# Facef.net
KiCad netlist of a schematic drawn in EAGLE
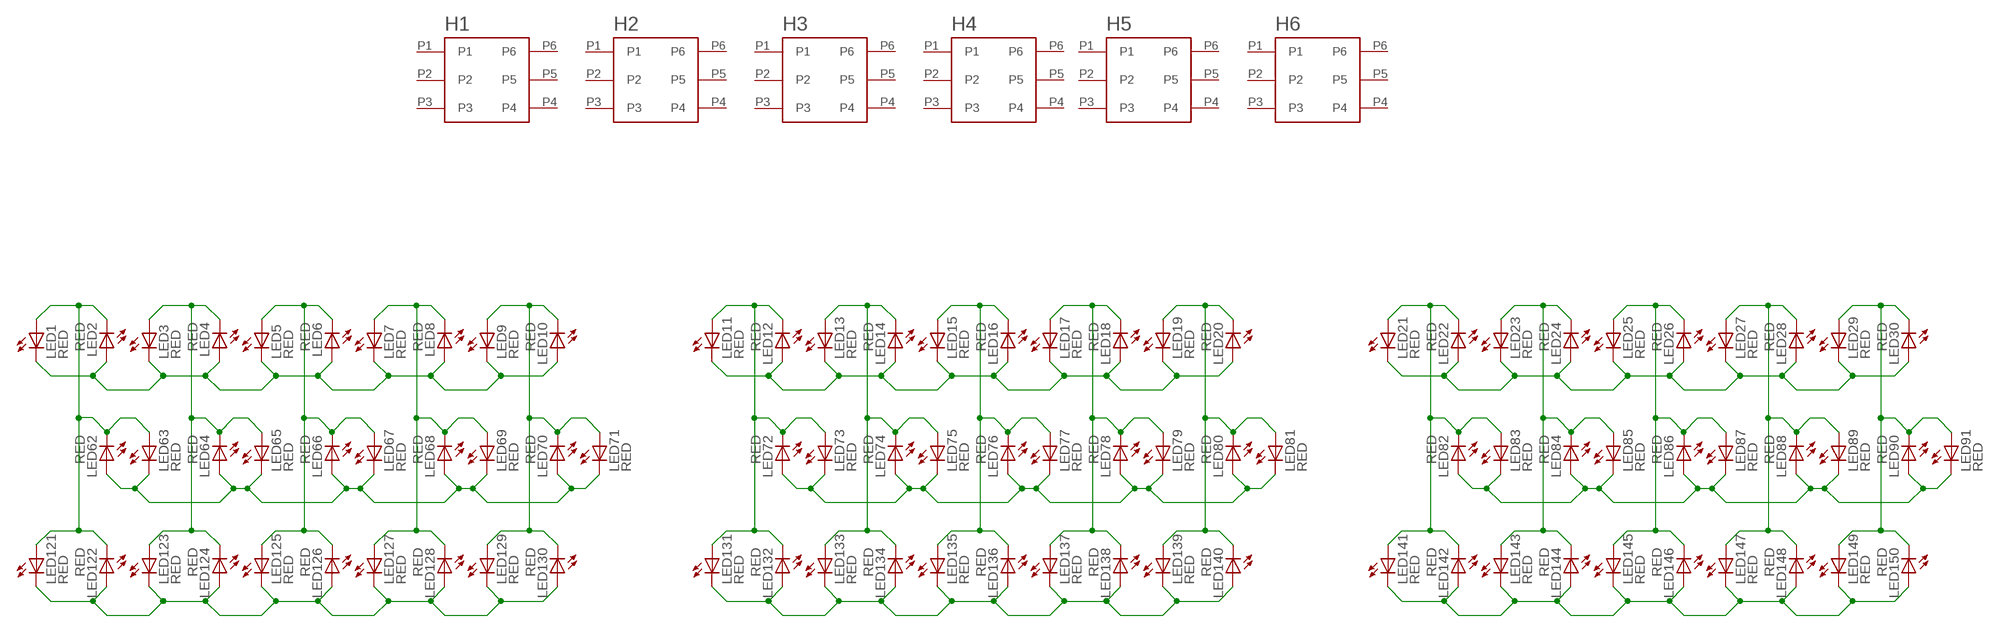
[diagram p0: schematic, sheet 1, part 1 of 2]
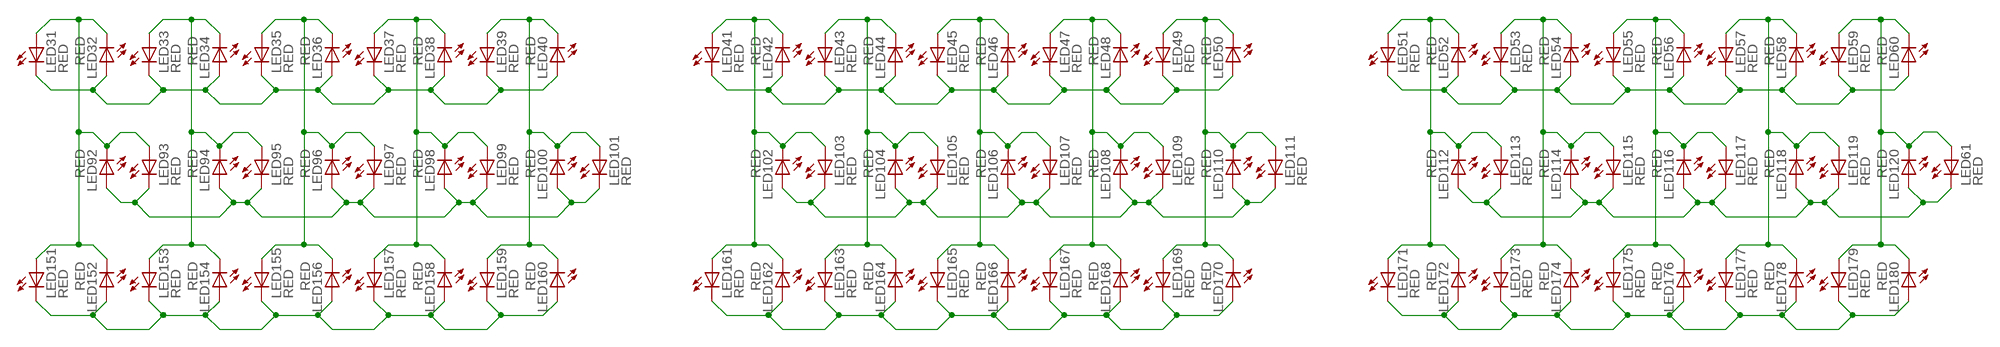
[diagram p1: schematic, sheet 1, part 2 of 2]

(export (version "E")
  (design (tool "Eeschema 10.0.6"))
  (components
    (comp (ref "H1")
      (value "2X3")
      (footprint "eagle-import:3X2_1MM_SMD")
      (libsource (lib "eagle-import") (part "2X3"))
    )
    (comp (ref "H2")
      (value "2X3")
      (footprint "eagle-import:3X2_1MM_SMD")
      (libsource (lib "eagle-import") (part "2X3"))
    )
    (comp (ref "H3")
      (value "2X3")
      (footprint "eagle-import:3X2_1MM_SMD")
      (libsource (lib "eagle-import") (part "2X3"))
    )
    (comp (ref "H4")
      (value "2X3")
      (footprint "eagle-import:3X2_1MM_SMD")
      (libsource (lib "eagle-import") (part "2X3"))
    )
    (comp (ref "H5")
      (value "2X3")
      (footprint "eagle-import:3X2_1MM_SMD")
      (libsource (lib "eagle-import") (part "2X3"))
    )
    (comp (ref "H6")
      (value "2X3")
      (footprint "eagle-import:3X2_1MM_SMD")
      (libsource (lib "eagle-import") (part "2X3"))
    )
    (comp (ref "LED1")
      (value "RED")
      (footprint "eagle-import:LED-0603")
      (libsource (lib "eagle-import") (part "LED0603"))
    )
    (comp (ref "LED2")
      (value "RED")
      (footprint "eagle-import:LED-0603")
      (libsource (lib "eagle-import") (part "LED0603"))
    )
    (comp (ref "LED3")
      (value "RED")
      (footprint "eagle-import:LED-0603")
      (libsource (lib "eagle-import") (part "LED0603"))
    )
    (comp (ref "LED4")
      (value "RED")
      (footprint "eagle-import:LED-0603")
      (libsource (lib "eagle-import") (part "LED0603"))
    )
    (comp (ref "LED5")
      (value "RED")
      (footprint "eagle-import:LED-0603")
      (libsource (lib "eagle-import") (part "LED0603"))
    )
    (comp (ref "LED6")
      (value "RED")
      (footprint "eagle-import:LED-0603")
      (libsource (lib "eagle-import") (part "LED0603"))
    )
    (comp (ref "LED7")
      (value "RED")
      (footprint "eagle-import:LED-0603")
      (libsource (lib "eagle-import") (part "LED0603"))
    )
    (comp (ref "LED8")
      (value "RED")
      (footprint "eagle-import:LED-0603")
      (libsource (lib "eagle-import") (part "LED0603"))
    )
    (comp (ref "LED9")
      (value "RED")
      (footprint "eagle-import:LED-0603")
      (libsource (lib "eagle-import") (part "LED0603"))
    )
    (comp (ref "LED10")
      (value "RED")
      (footprint "eagle-import:LED-0603")
      (libsource (lib "eagle-import") (part "LED0603"))
    )
    (comp (ref "LED11")
      (value "RED")
      (footprint "eagle-import:LED-0603")
      (libsource (lib "eagle-import") (part "LED0603"))
    )
    (comp (ref "LED12")
      (value "RED")
      (footprint "eagle-import:LED-0603")
      (libsource (lib "eagle-import") (part "LED0603"))
    )
    (comp (ref "LED13")
      (value "RED")
      (footprint "eagle-import:LED-0603")
      (libsource (lib "eagle-import") (part "LED0603"))
    )
    (comp (ref "LED14")
      (value "RED")
      (footprint "eagle-import:LED-0603")
      (libsource (lib "eagle-import") (part "LED0603"))
    )
    (comp (ref "LED15")
      (value "RED")
      (footprint "eagle-import:LED-0603")
      (libsource (lib "eagle-import") (part "LED0603"))
    )
    (comp (ref "LED16")
      (value "RED")
      (footprint "eagle-import:LED-0603")
      (libsource (lib "eagle-import") (part "LED0603"))
    )
    (comp (ref "LED17")
      (value "RED")
      (footprint "eagle-import:LED-0603")
      (libsource (lib "eagle-import") (part "LED0603"))
    )
    (comp (ref "LED18")
      (value "RED")
      (footprint "eagle-import:LED-0603")
      (libsource (lib "eagle-import") (part "LED0603"))
    )
    (comp (ref "LED19")
      (value "RED")
      (footprint "eagle-import:LED-0603")
      (libsource (lib "eagle-import") (part "LED0603"))
    )
    (comp (ref "LED20")
      (value "RED")
      (footprint "eagle-import:LED-0603")
      (libsource (lib "eagle-import") (part "LED0603"))
    )
    (comp (ref "LED21")
      (value "RED")
      (footprint "eagle-import:LED-0603")
      (libsource (lib "eagle-import") (part "LED0603"))
    )
    (comp (ref "LED22")
      (value "RED")
      (footprint "eagle-import:LED-0603")
      (libsource (lib "eagle-import") (part "LED0603"))
    )
    (comp (ref "LED23")
      (value "RED")
      (footprint "eagle-import:LED-0603")
      (libsource (lib "eagle-import") (part "LED0603"))
    )
    (comp (ref "LED24")
      (value "RED")
      (footprint "eagle-import:LED-0603")
      (libsource (lib "eagle-import") (part "LED0603"))
    )
    (comp (ref "LED25")
      (value "RED")
      (footprint "eagle-import:LED-0603")
      (libsource (lib "eagle-import") (part "LED0603"))
    )
    (comp (ref "LED26")
      (value "RED")
      (footprint "eagle-import:LED-0603")
      (libsource (lib "eagle-import") (part "LED0603"))
    )
    (comp (ref "LED27")
      (value "RED")
      (footprint "eagle-import:LED-0603")
      (libsource (lib "eagle-import") (part "LED0603"))
    )
    (comp (ref "LED28")
      (value "RED")
      (footprint "eagle-import:LED-0603")
      (libsource (lib "eagle-import") (part "LED0603"))
    )
    (comp (ref "LED29")
      (value "RED")
      (footprint "eagle-import:LED-0603")
      (libsource (lib "eagle-import") (part "LED0603"))
    )
    (comp (ref "LED30")
      (value "RED")
      (footprint "eagle-import:LED-0603")
      (libsource (lib "eagle-import") (part "LED0603"))
    )
    (comp (ref "LED31")
      (value "RED")
      (footprint "eagle-import:LED-0603")
      (libsource (lib "eagle-import") (part "LED0603"))
    )
    (comp (ref "LED32")
      (value "RED")
      (footprint "eagle-import:LED-0603")
      (libsource (lib "eagle-import") (part "LED0603"))
    )
    (comp (ref "LED33")
      (value "RED")
      (footprint "eagle-import:LED-0603")
      (libsource (lib "eagle-import") (part "LED0603"))
    )
    (comp (ref "LED34")
      (value "RED")
      (footprint "eagle-import:LED-0603")
      (libsource (lib "eagle-import") (part "LED0603"))
    )
    (comp (ref "LED35")
      (value "RED")
      (footprint "eagle-import:LED-0603")
      (libsource (lib "eagle-import") (part "LED0603"))
    )
    (comp (ref "LED36")
      (value "RED")
      (footprint "eagle-import:LED-0603")
      (libsource (lib "eagle-import") (part "LED0603"))
    )
    (comp (ref "LED37")
      (value "RED")
      (footprint "eagle-import:LED-0603")
      (libsource (lib "eagle-import") (part "LED0603"))
    )
    (comp (ref "LED38")
      (value "RED")
      (footprint "eagle-import:LED-0603")
      (libsource (lib "eagle-import") (part "LED0603"))
    )
    (comp (ref "LED39")
      (value "RED")
      (footprint "eagle-import:LED-0603")
      (libsource (lib "eagle-import") (part "LED0603"))
    )
    (comp (ref "LED40")
      (value "RED")
      (footprint "eagle-import:LED-0603")
      (libsource (lib "eagle-import") (part "LED0603"))
    )
    (comp (ref "LED41")
      (value "RED")
      (footprint "eagle-import:LED-0603")
      (libsource (lib "eagle-import") (part "LED0603"))
    )
    (comp (ref "LED42")
      (value "RED")
      (footprint "eagle-import:LED-0603")
      (libsource (lib "eagle-import") (part "LED0603"))
    )
    (comp (ref "LED43")
      (value "RED")
      (footprint "eagle-import:LED-0603")
      (libsource (lib "eagle-import") (part "LED0603"))
    )
    (comp (ref "LED44")
      (value "RED")
      (footprint "eagle-import:LED-0603")
      (libsource (lib "eagle-import") (part "LED0603"))
    )
    (comp (ref "LED45")
      (value "RED")
      (footprint "eagle-import:LED-0603")
      (libsource (lib "eagle-import") (part "LED0603"))
    )
    (comp (ref "LED46")
      (value "RED")
      (footprint "eagle-import:LED-0603")
      (libsource (lib "eagle-import") (part "LED0603"))
    )
    (comp (ref "LED47")
      (value "RED")
      (footprint "eagle-import:LED-0603")
      (libsource (lib "eagle-import") (part "LED0603"))
    )
    (comp (ref "LED48")
      (value "RED")
      (footprint "eagle-import:LED-0603")
      (libsource (lib "eagle-import") (part "LED0603"))
    )
    (comp (ref "LED49")
      (value "RED")
      (footprint "eagle-import:LED-0603")
      (libsource (lib "eagle-import") (part "LED0603"))
    )
    (comp (ref "LED50")
      (value "RED")
      (footprint "eagle-import:LED-0603")
      (libsource (lib "eagle-import") (part "LED0603"))
    )
    (comp (ref "LED51")
      (value "RED")
      (footprint "eagle-import:LED-0603")
      (libsource (lib "eagle-import") (part "LED0603"))
    )
    (comp (ref "LED52")
      (value "RED")
      (footprint "eagle-import:LED-0603")
      (libsource (lib "eagle-import") (part "LED0603"))
    )
    (comp (ref "LED53")
      (value "RED")
      (footprint "eagle-import:LED-0603")
      (libsource (lib "eagle-import") (part "LED0603"))
    )
    (comp (ref "LED54")
      (value "RED")
      (footprint "eagle-import:LED-0603")
      (libsource (lib "eagle-import") (part "LED0603"))
    )
    (comp (ref "LED55")
      (value "RED")
      (footprint "eagle-import:LED-0603")
      (libsource (lib "eagle-import") (part "LED0603"))
    )
    (comp (ref "LED56")
      (value "RED")
      (footprint "eagle-import:LED-0603")
      (libsource (lib "eagle-import") (part "LED0603"))
    )
    (comp (ref "LED57")
      (value "RED")
      (footprint "eagle-import:LED-0603")
      (libsource (lib "eagle-import") (part "LED0603"))
    )
    (comp (ref "LED58")
      (value "RED")
      (footprint "eagle-import:LED-0603")
      (libsource (lib "eagle-import") (part "LED0603"))
    )
    (comp (ref "LED59")
      (value "RED")
      (footprint "eagle-import:LED-0603")
      (libsource (lib "eagle-import") (part "LED0603"))
    )
    (comp (ref "LED60")
      (value "RED")
      (footprint "eagle-import:LED-0603")
      (libsource (lib "eagle-import") (part "LED0603"))
    )
    (comp (ref "LED61")
      (value "RED")
      (footprint "eagle-import:LED-0603")
      (libsource (lib "eagle-import") (part "LED0603"))
    )
    (comp (ref "LED62")
      (value "RED")
      (footprint "eagle-import:LED-0603")
      (libsource (lib "eagle-import") (part "LED0603"))
    )
    (comp (ref "LED63")
      (value "RED")
      (footprint "eagle-import:LED-0603")
      (libsource (lib "eagle-import") (part "LED0603"))
    )
    (comp (ref "LED64")
      (value "RED")
      (footprint "eagle-import:LED-0603")
      (libsource (lib "eagle-import") (part "LED0603"))
    )
    (comp (ref "LED65")
      (value "RED")
      (footprint "eagle-import:LED-0603")
      (libsource (lib "eagle-import") (part "LED0603"))
    )
    (comp (ref "LED66")
      (value "RED")
      (footprint "eagle-import:LED-0603")
      (libsource (lib "eagle-import") (part "LED0603"))
    )
    (comp (ref "LED67")
      (value "RED")
      (footprint "eagle-import:LED-0603")
      (libsource (lib "eagle-import") (part "LED0603"))
    )
    (comp (ref "LED68")
      (value "RED")
      (footprint "eagle-import:LED-0603")
      (libsource (lib "eagle-import") (part "LED0603"))
    )
    (comp (ref "LED69")
      (value "RED")
      (footprint "eagle-import:LED-0603")
      (libsource (lib "eagle-import") (part "LED0603"))
    )
    (comp (ref "LED70")
      (value "RED")
      (footprint "eagle-import:LED-0603")
      (libsource (lib "eagle-import") (part "LED0603"))
    )
    (comp (ref "LED71")
      (value "RED")
      (footprint "eagle-import:LED-0603")
      (libsource (lib "eagle-import") (part "LED0603"))
    )
    (comp (ref "LED72")
      (value "RED")
      (footprint "eagle-import:LED-0603")
      (libsource (lib "eagle-import") (part "LED0603"))
    )
    (comp (ref "LED73")
      (value "RED")
      (footprint "eagle-import:LED-0603")
      (libsource (lib "eagle-import") (part "LED0603"))
    )
    (comp (ref "LED74")
      (value "RED")
      (footprint "eagle-import:LED-0603")
      (libsource (lib "eagle-import") (part "LED0603"))
    )
    (comp (ref "LED75")
      (value "RED")
      (footprint "eagle-import:LED-0603")
      (libsource (lib "eagle-import") (part "LED0603"))
    )
    (comp (ref "LED76")
      (value "RED")
      (footprint "eagle-import:LED-0603")
      (libsource (lib "eagle-import") (part "LED0603"))
    )
    (comp (ref "LED77")
      (value "RED")
      (footprint "eagle-import:LED-0603")
      (libsource (lib "eagle-import") (part "LED0603"))
    )
    (comp (ref "LED78")
      (value "RED")
      (footprint "eagle-import:LED-0603")
      (libsource (lib "eagle-import") (part "LED0603"))
    )
    (comp (ref "LED79")
      (value "RED")
      (footprint "eagle-import:LED-0603")
      (libsource (lib "eagle-import") (part "LED0603"))
    )
    (comp (ref "LED80")
      (value "RED")
      (footprint "eagle-import:LED-0603")
      (libsource (lib "eagle-import") (part "LED0603"))
    )
    (comp (ref "LED81")
      (value "RED")
      (footprint "eagle-import:LED-0603")
      (libsource (lib "eagle-import") (part "LED0603"))
    )
    (comp (ref "LED82")
      (value "RED")
      (footprint "eagle-import:LED-0603")
      (libsource (lib "eagle-import") (part "LED0603"))
    )
    (comp (ref "LED83")
      (value "RED")
      (footprint "eagle-import:LED-0603")
      (libsource (lib "eagle-import") (part "LED0603"))
    )
    (comp (ref "LED84")
      (value "RED")
      (footprint "eagle-import:LED-0603")
      (libsource (lib "eagle-import") (part "LED0603"))
    )
    (comp (ref "LED85")
      (value "RED")
      (footprint "eagle-import:LED-0603")
      (libsource (lib "eagle-import") (part "LED0603"))
    )
    (comp (ref "LED86")
      (value "RED")
      (footprint "eagle-import:LED-0603")
      (libsource (lib "eagle-import") (part "LED0603"))
    )
    (comp (ref "LED87")
      (value "RED")
      (footprint "eagle-import:LED-0603")
      (libsource (lib "eagle-import") (part "LED0603"))
    )
    (comp (ref "LED88")
      (value "RED")
      (footprint "eagle-import:LED-0603")
      (libsource (lib "eagle-import") (part "LED0603"))
    )
    (comp (ref "LED89")
      (value "RED")
      (footprint "eagle-import:LED-0603")
      (libsource (lib "eagle-import") (part "LED0603"))
    )
    (comp (ref "LED90")
      (value "RED")
      (footprint "eagle-import:LED-0603")
      (libsource (lib "eagle-import") (part "LED0603"))
    )
    (comp (ref "LED91")
      (value "RED")
      (footprint "eagle-import:LED-0603")
      (libsource (lib "eagle-import") (part "LED0603"))
    )
    (comp (ref "LED92")
      (value "RED")
      (footprint "eagle-import:LED-0603")
      (libsource (lib "eagle-import") (part "LED0603"))
    )
    (comp (ref "LED93")
      (value "RED")
      (footprint "eagle-import:LED-0603")
      (libsource (lib "eagle-import") (part "LED0603"))
    )
    (comp (ref "LED94")
      (value "RED")
      (footprint "eagle-import:LED-0603")
      (libsource (lib "eagle-import") (part "LED0603"))
    )
    (comp (ref "LED95")
      (value "RED")
      (footprint "eagle-import:LED-0603")
      (libsource (lib "eagle-import") (part "LED0603"))
    )
    (comp (ref "LED96")
      (value "RED")
      (footprint "eagle-import:LED-0603")
      (libsource (lib "eagle-import") (part "LED0603"))
    )
    (comp (ref "LED97")
      (value "RED")
      (footprint "eagle-import:LED-0603")
      (libsource (lib "eagle-import") (part "LED0603"))
    )
    (comp (ref "LED98")
      (value "RED")
      (footprint "eagle-import:LED-0603")
      (libsource (lib "eagle-import") (part "LED0603"))
    )
    (comp (ref "LED99")
      (value "RED")
      (footprint "eagle-import:LED-0603")
      (libsource (lib "eagle-import") (part "LED0603"))
    )
    (comp (ref "LED100")
      (value "RED")
      (footprint "eagle-import:LED-0603")
      (libsource (lib "eagle-import") (part "LED0603"))
    )
    (comp (ref "LED101")
      (value "RED")
      (footprint "eagle-import:LED-0603")
      (libsource (lib "eagle-import") (part "LED0603"))
    )
    (comp (ref "LED102")
      (value "RED")
      (footprint "eagle-import:LED-0603")
      (libsource (lib "eagle-import") (part "LED0603"))
    )
    (comp (ref "LED103")
      (value "RED")
      (footprint "eagle-import:LED-0603")
      (libsource (lib "eagle-import") (part "LED0603"))
    )
    (comp (ref "LED104")
      (value "RED")
      (footprint "eagle-import:LED-0603")
      (libsource (lib "eagle-import") (part "LED0603"))
    )
    (comp (ref "LED105")
      (value "RED")
      (footprint "eagle-import:LED-0603")
      (libsource (lib "eagle-import") (part "LED0603"))
    )
    (comp (ref "LED106")
      (value "RED")
      (footprint "eagle-import:LED-0603")
      (libsource (lib "eagle-import") (part "LED0603"))
    )
    (comp (ref "LED107")
      (value "RED")
      (footprint "eagle-import:LED-0603")
      (libsource (lib "eagle-import") (part "LED0603"))
    )
    (comp (ref "LED108")
      (value "RED")
      (footprint "eagle-import:LED-0603")
      (libsource (lib "eagle-import") (part "LED0603"))
    )
    (comp (ref "LED109")
      (value "RED")
      (footprint "eagle-import:LED-0603")
      (libsource (lib "eagle-import") (part "LED0603"))
    )
    (comp (ref "LED110")
      (value "RED")
      (footprint "eagle-import:LED-0603")
      (libsource (lib "eagle-import") (part "LED0603"))
    )
    (comp (ref "LED111")
      (value "RED")
      (footprint "eagle-import:LED-0603")
      (libsource (lib "eagle-import") (part "LED0603"))
    )
    (comp (ref "LED112")
      (value "RED")
      (footprint "eagle-import:LED-0603")
      (libsource (lib "eagle-import") (part "LED0603"))
    )
    (comp (ref "LED113")
      (value "RED")
      (footprint "eagle-import:LED-0603")
      (libsource (lib "eagle-import") (part "LED0603"))
    )
    (comp (ref "LED114")
      (value "RED")
      (footprint "eagle-import:LED-0603")
      (libsource (lib "eagle-import") (part "LED0603"))
    )
    (comp (ref "LED115")
      (value "RED")
      (footprint "eagle-import:LED-0603")
      (libsource (lib "eagle-import") (part "LED0603"))
    )
    (comp (ref "LED116")
      (value "RED")
      (footprint "eagle-import:LED-0603")
      (libsource (lib "eagle-import") (part "LED0603"))
    )
    (comp (ref "LED117")
      (value "RED")
      (footprint "eagle-import:LED-0603")
      (libsource (lib "eagle-import") (part "LED0603"))
    )
    (comp (ref "LED118")
      (value "RED")
      (footprint "eagle-import:LED-0603")
      (libsource (lib "eagle-import") (part "LED0603"))
    )
    (comp (ref "LED119")
      (value "RED")
      (footprint "eagle-import:LED-0603")
      (libsource (lib "eagle-import") (part "LED0603"))
    )
    (comp (ref "LED120")
      (value "RED")
      (footprint "eagle-import:LED-0603")
      (libsource (lib "eagle-import") (part "LED0603"))
    )
    (comp (ref "LED121")
      (value "RED")
      (footprint "eagle-import:LED-0603")
      (libsource (lib "eagle-import") (part "LED0603"))
    )
    (comp (ref "LED122")
      (value "RED")
      (footprint "eagle-import:LED-0603")
      (libsource (lib "eagle-import") (part "LED0603"))
    )
    (comp (ref "LED123")
      (value "RED")
      (footprint "eagle-import:LED-0603")
      (libsource (lib "eagle-import") (part "LED0603"))
    )
    (comp (ref "LED124")
      (value "RED")
      (footprint "eagle-import:LED-0603")
      (libsource (lib "eagle-import") (part "LED0603"))
    )
    (comp (ref "LED125")
      (value "RED")
      (footprint "eagle-import:LED-0603")
      (libsource (lib "eagle-import") (part "LED0603"))
    )
    (comp (ref "LED126")
      (value "RED")
      (footprint "eagle-import:LED-0603")
      (libsource (lib "eagle-import") (part "LED0603"))
    )
    (comp (ref "LED127")
      (value "RED")
      (footprint "eagle-import:LED-0603")
      (libsource (lib "eagle-import") (part "LED0603"))
    )
    (comp (ref "LED128")
      (value "RED")
      (footprint "eagle-import:LED-0603")
      (libsource (lib "eagle-import") (part "LED0603"))
    )
    (comp (ref "LED129")
      (value "RED")
      (footprint "eagle-import:LED-0603")
      (libsource (lib "eagle-import") (part "LED0603"))
    )
    (comp (ref "LED130")
      (value "RED")
      (footprint "eagle-import:LED-0603")
      (libsource (lib "eagle-import") (part "LED0603"))
    )
    (comp (ref "LED131")
      (value "RED")
      (footprint "eagle-import:LED-0603")
      (libsource (lib "eagle-import") (part "LED0603"))
    )
    (comp (ref "LED132")
      (value "RED")
      (footprint "eagle-import:LED-0603")
      (libsource (lib "eagle-import") (part "LED0603"))
    )
    (comp (ref "LED133")
      (value "RED")
      (footprint "eagle-import:LED-0603")
      (libsource (lib "eagle-import") (part "LED0603"))
    )
    (comp (ref "LED134")
      (value "RED")
      (footprint "eagle-import:LED-0603")
      (libsource (lib "eagle-import") (part "LED0603"))
    )
    (comp (ref "LED135")
      (value "RED")
      (footprint "eagle-import:LED-0603")
      (libsource (lib "eagle-import") (part "LED0603"))
    )
    (comp (ref "LED136")
      (value "RED")
      (footprint "eagle-import:LED-0603")
      (libsource (lib "eagle-import") (part "LED0603"))
    )
    (comp (ref "LED137")
      (value "RED")
      (footprint "eagle-import:LED-0603")
      (libsource (lib "eagle-import") (part "LED0603"))
    )
    (comp (ref "LED138")
      (value "RED")
      (footprint "eagle-import:LED-0603")
      (libsource (lib "eagle-import") (part "LED0603"))
    )
    (comp (ref "LED139")
      (value "RED")
      (footprint "eagle-import:LED-0603")
      (libsource (lib "eagle-import") (part "LED0603"))
    )
    (comp (ref "LED140")
      (value "RED")
      (footprint "eagle-import:LED-0603")
      (libsource (lib "eagle-import") (part "LED0603"))
    )
    (comp (ref "LED141")
      (value "RED")
      (footprint "eagle-import:LED-0603")
      (libsource (lib "eagle-import") (part "LED0603"))
    )
    (comp (ref "LED142")
      (value "RED")
      (footprint "eagle-import:LED-0603")
      (libsource (lib "eagle-import") (part "LED0603"))
    )
    (comp (ref "LED143")
      (value "RED")
      (footprint "eagle-import:LED-0603")
      (libsource (lib "eagle-import") (part "LED0603"))
    )
    (comp (ref "LED144")
      (value "RED")
      (footprint "eagle-import:LED-0603")
      (libsource (lib "eagle-import") (part "LED0603"))
    )
    (comp (ref "LED145")
      (value "RED")
      (footprint "eagle-import:LED-0603")
      (libsource (lib "eagle-import") (part "LED0603"))
    )
    (comp (ref "LED146")
      (value "RED")
      (footprint "eagle-import:LED-0603")
      (libsource (lib "eagle-import") (part "LED0603"))
    )
    (comp (ref "LED147")
      (value "RED")
      (footprint "eagle-import:LED-0603")
      (libsource (lib "eagle-import") (part "LED0603"))
    )
    (comp (ref "LED148")
      (value "RED")
      (footprint "eagle-import:LED-0603")
      (libsource (lib "eagle-import") (part "LED0603"))
    )
    (comp (ref "LED149")
      (value "RED")
      (footprint "eagle-import:LED-0603")
      (libsource (lib "eagle-import") (part "LED0603"))
    )
    (comp (ref "LED150")
      (value "RED")
      (footprint "eagle-import:LED-0603")
      (libsource (lib "eagle-import") (part "LED0603"))
    )
    (comp (ref "LED151")
      (value "RED")
      (footprint "eagle-import:LED-0603")
      (libsource (lib "eagle-import") (part "LED0603"))
    )
    (comp (ref "LED152")
      (value "RED")
      (footprint "eagle-import:LED-0603")
      (libsource (lib "eagle-import") (part "LED0603"))
    )
    (comp (ref "LED153")
      (value "RED")
      (footprint "eagle-import:LED-0603")
      (libsource (lib "eagle-import") (part "LED0603"))
    )
    (comp (ref "LED154")
      (value "RED")
      (footprint "eagle-import:LED-0603")
      (libsource (lib "eagle-import") (part "LED0603"))
    )
    (comp (ref "LED155")
      (value "RED")
      (footprint "eagle-import:LED-0603")
      (libsource (lib "eagle-import") (part "LED0603"))
    )
    (comp (ref "LED156")
      (value "RED")
      (footprint "eagle-import:LED-0603")
      (libsource (lib "eagle-import") (part "LED0603"))
    )
    (comp (ref "LED157")
      (value "RED")
      (footprint "eagle-import:LED-0603")
      (libsource (lib "eagle-import") (part "LED0603"))
    )
    (comp (ref "LED158")
      (value "RED")
      (footprint "eagle-import:LED-0603")
      (libsource (lib "eagle-import") (part "LED0603"))
    )
    (comp (ref "LED159")
      (value "RED")
      (footprint "eagle-import:LED-0603")
      (libsource (lib "eagle-import") (part "LED0603"))
    )
    (comp (ref "LED160")
      (value "RED")
      (footprint "eagle-import:LED-0603")
      (libsource (lib "eagle-import") (part "LED0603"))
    )
    (comp (ref "LED161")
      (value "RED")
      (footprint "eagle-import:LED-0603")
      (libsource (lib "eagle-import") (part "LED0603"))
    )
    (comp (ref "LED162")
      (value "RED")
      (footprint "eagle-import:LED-0603")
      (libsource (lib "eagle-import") (part "LED0603"))
    )
    (comp (ref "LED163")
      (value "RED")
      (footprint "eagle-import:LED-0603")
      (libsource (lib "eagle-import") (part "LED0603"))
    )
    (comp (ref "LED164")
      (value "RED")
      (footprint "eagle-import:LED-0603")
      (libsource (lib "eagle-import") (part "LED0603"))
    )
    (comp (ref "LED165")
      (value "RED")
      (footprint "eagle-import:LED-0603")
      (libsource (lib "eagle-import") (part "LED0603"))
    )
    (comp (ref "LED166")
      (value "RED")
      (footprint "eagle-import:LED-0603")
      (libsource (lib "eagle-import") (part "LED0603"))
    )
    (comp (ref "LED167")
      (value "RED")
      (footprint "eagle-import:LED-0603")
      (libsource (lib "eagle-import") (part "LED0603"))
    )
    (comp (ref "LED168")
      (value "RED")
      (footprint "eagle-import:LED-0603")
      (libsource (lib "eagle-import") (part "LED0603"))
    )
    (comp (ref "LED169")
      (value "RED")
      (footprint "eagle-import:LED-0603")
      (libsource (lib "eagle-import") (part "LED0603"))
    )
    (comp (ref "LED170")
      (value "RED")
      (footprint "eagle-import:LED-0603")
      (libsource (lib "eagle-import") (part "LED0603"))
    )
    (comp (ref "LED171")
      (value "RED")
      (footprint "eagle-import:LED-0603")
      (libsource (lib "eagle-import") (part "LED0603"))
    )
    (comp (ref "LED172")
      (value "RED")
      (footprint "eagle-import:LED-0603")
      (libsource (lib "eagle-import") (part "LED0603"))
    )
    (comp (ref "LED173")
      (value "RED")
      (footprint "eagle-import:LED-0603")
      (libsource (lib "eagle-import") (part "LED0603"))
    )
    (comp (ref "LED174")
      (value "RED")
      (footprint "eagle-import:LED-0603")
      (libsource (lib "eagle-import") (part "LED0603"))
    )
    (comp (ref "LED175")
      (value "RED")
      (footprint "eagle-import:LED-0603")
      (libsource (lib "eagle-import") (part "LED0603"))
    )
    (comp (ref "LED176")
      (value "RED")
      (footprint "eagle-import:LED-0603")
      (libsource (lib "eagle-import") (part "LED0603"))
    )
    (comp (ref "LED177")
      (value "RED")
      (footprint "eagle-import:LED-0603")
      (libsource (lib "eagle-import") (part "LED0603"))
    )
    (comp (ref "LED178")
      (value "RED")
      (footprint "eagle-import:LED-0603")
      (libsource (lib "eagle-import") (part "LED0603"))
    )
    (comp (ref "LED179")
      (value "RED")
      (footprint "eagle-import:LED-0603")
      (libsource (lib "eagle-import") (part "LED0603"))
    )
    (comp (ref "LED180")
      (value "RED")
      (footprint "eagle-import:LED-0603")
      (libsource (lib "eagle-import") (part "LED0603"))
    )
  )
  (nets
    (net (code "1") (name "Net-(LED1-PadA)") (class "Default")
      (node (ref "LED1") (pin "A") (pinfunction "A_A") (pintype "passive"))
      (node (ref "LED121") (pin "A") (pinfunction "A_A") (pintype "passive"))
      (node (ref "LED122") (pin "C") (pinfunction "C_C") (pintype "passive"))
      (node (ref "LED2") (pin "C") (pinfunction "C_C") (pintype "passive"))
      (node (ref "LED62") (pin "C") (pinfunction "C_C") (pintype "passive"))
      (node (ref "LED63") (pin "A") (pinfunction "A_A") (pintype "passive"))
    )
    (net (code "2") (name "Net-(LED1-PadC)") (class "Default")
      (node (ref "LED1") (pin "C") (pinfunction "C_C") (pintype "passive"))
      (node (ref "LED10") (pin "A") (pinfunction "A_A") (pintype "passive"))
      (node (ref "LED2") (pin "A") (pinfunction "A_A") (pintype "passive"))
      (node (ref "LED3") (pin "C") (pinfunction "C_C") (pintype "passive"))
      (node (ref "LED4") (pin "A") (pinfunction "A_A") (pintype "passive"))
      (node (ref "LED5") (pin "C") (pinfunction "C_C") (pintype "passive"))
      (node (ref "LED6") (pin "A") (pinfunction "A_A") (pintype "passive"))
      (node (ref "LED7") (pin "C") (pinfunction "C_C") (pintype "passive"))
      (node (ref "LED8") (pin "A") (pinfunction "A_A") (pintype "passive"))
      (node (ref "LED9") (pin "C") (pinfunction "C_C") (pintype "passive"))
    )
    (net (code "3") (name "Net-(LED10-PadC)") (class "Default")
      (node (ref "LED10") (pin "C") (pinfunction "C_C") (pintype "passive"))
      (node (ref "LED129") (pin "A") (pinfunction "A_A") (pintype "passive"))
      (node (ref "LED130") (pin "C") (pinfunction "C_C") (pintype "passive"))
      (node (ref "LED70") (pin "C") (pinfunction "C_C") (pintype "passive"))
      (node (ref "LED71") (pin "A") (pinfunction "A_A") (pintype "passive"))
      (node (ref "LED9") (pin "A") (pinfunction "A_A") (pintype "passive"))
    )
    (net (code "4") (name "Net-(LED11-PadA)") (class "Default")
      (node (ref "LED11") (pin "A") (pinfunction "A_A") (pintype "passive"))
      (node (ref "LED12") (pin "C") (pinfunction "C_C") (pintype "passive"))
      (node (ref "LED131") (pin "A") (pinfunction "A_A") (pintype "passive"))
      (node (ref "LED132") (pin "C") (pinfunction "C_C") (pintype "passive"))
      (node (ref "LED72") (pin "C") (pinfunction "C_C") (pintype "passive"))
      (node (ref "LED73") (pin "A") (pinfunction "A_A") (pintype "passive"))
    )
    (net (code "5") (name "Net-(LED11-PadC)") (class "Default")
      (node (ref "LED11") (pin "C") (pinfunction "C_C") (pintype "passive"))
      (node (ref "LED12") (pin "A") (pinfunction "A_A") (pintype "passive"))
      (node (ref "LED13") (pin "C") (pinfunction "C_C") (pintype "passive"))
      (node (ref "LED14") (pin "A") (pinfunction "A_A") (pintype "passive"))
      (node (ref "LED15") (pin "C") (pinfunction "C_C") (pintype "passive"))
      (node (ref "LED16") (pin "A") (pinfunction "A_A") (pintype "passive"))
      (node (ref "LED17") (pin "C") (pinfunction "C_C") (pintype "passive"))
      (node (ref "LED18") (pin "A") (pinfunction "A_A") (pintype "passive"))
      (node (ref "LED19") (pin "C") (pinfunction "C_C") (pintype "passive"))
      (node (ref "LED20") (pin "A") (pinfunction "A_A") (pintype "passive"))
    )
    (net (code "6") (name "Net-(LED13-PadA)") (class "Default")
      (node (ref "LED13") (pin "A") (pinfunction "A_A") (pintype "passive"))
      (node (ref "LED133") (pin "A") (pinfunction "A_A") (pintype "passive"))
      (node (ref "LED134") (pin "C") (pinfunction "C_C") (pintype "passive"))
      (node (ref "LED14") (pin "C") (pinfunction "C_C") (pintype "passive"))
      (node (ref "LED74") (pin "C") (pinfunction "C_C") (pintype "passive"))
      (node (ref "LED75") (pin "A") (pinfunction "A_A") (pintype "passive"))
    )
    (net (code "7") (name "Net-(LED21-PadC)") (class "Default")
      (node (ref "LED21") (pin "C") (pinfunction "C_C") (pintype "passive"))
      (node (ref "LED22") (pin "A") (pinfunction "A_A") (pintype "passive"))
      (node (ref "LED23") (pin "C") (pinfunction "C_C") (pintype "passive"))
      (node (ref "LED24") (pin "A") (pinfunction "A_A") (pintype "passive"))
      (node (ref "LED25") (pin "C") (pinfunction "C_C") (pintype "passive"))
      (node (ref "LED26") (pin "A") (pinfunction "A_A") (pintype "passive"))
      (node (ref "LED27") (pin "C") (pinfunction "C_C") (pintype "passive"))
      (node (ref "LED28") (pin "A") (pinfunction "A_A") (pintype "passive"))
      (node (ref "LED29") (pin "C") (pinfunction "C_C") (pintype "passive"))
      (node (ref "LED30") (pin "A") (pinfunction "A_A") (pintype "passive"))
    )
    (net (code "8") (name "Net-(LED31-PadC)") (class "Default")
      (node (ref "LED31") (pin "C") (pinfunction "C_C") (pintype "passive"))
      (node (ref "LED32") (pin "A") (pinfunction "A_A") (pintype "passive"))
      (node (ref "LED33") (pin "C") (pinfunction "C_C") (pintype "passive"))
      (node (ref "LED34") (pin "A") (pinfunction "A_A") (pintype "passive"))
      (node (ref "LED35") (pin "C") (pinfunction "C_C") (pintype "passive"))
      (node (ref "LED36") (pin "A") (pinfunction "A_A") (pintype "passive"))
      (node (ref "LED37") (pin "C") (pinfunction "C_C") (pintype "passive"))
      (node (ref "LED38") (pin "A") (pinfunction "A_A") (pintype "passive"))
      (node (ref "LED39") (pin "C") (pinfunction "C_C") (pintype "passive"))
      (node (ref "LED40") (pin "A") (pinfunction "A_A") (pintype "passive"))
    )
    (net (code "9") (name "Net-(LED41-PadC)") (class "Default")
      (node (ref "LED41") (pin "C") (pinfunction "C_C") (pintype "passive"))
      (node (ref "LED42") (pin "A") (pinfunction "A_A") (pintype "passive"))
      (node (ref "LED43") (pin "C") (pinfunction "C_C") (pintype "passive"))
      (node (ref "LED44") (pin "A") (pinfunction "A_A") (pintype "passive"))
      (node (ref "LED45") (pin "C") (pinfunction "C_C") (pintype "passive"))
      (node (ref "LED46") (pin "A") (pinfunction "A_A") (pintype "passive"))
      (node (ref "LED47") (pin "C") (pinfunction "C_C") (pintype "passive"))
      (node (ref "LED48") (pin "A") (pinfunction "A_A") (pintype "passive"))
      (node (ref "LED49") (pin "C") (pinfunction "C_C") (pintype "passive"))
      (node (ref "LED50") (pin "A") (pinfunction "A_A") (pintype "passive"))
    )
    (net (code "10") (name "Net-(LED51-PadC)") (class "Default")
      (node (ref "LED51") (pin "C") (pinfunction "C_C") (pintype "passive"))
      (node (ref "LED52") (pin "A") (pinfunction "A_A") (pintype "passive"))
      (node (ref "LED53") (pin "C") (pinfunction "C_C") (pintype "passive"))
      (node (ref "LED54") (pin "A") (pinfunction "A_A") (pintype "passive"))
      (node (ref "LED55") (pin "C") (pinfunction "C_C") (pintype "passive"))
      (node (ref "LED56") (pin "A") (pinfunction "A_A") (pintype "passive"))
      (node (ref "LED57") (pin "C") (pinfunction "C_C") (pintype "passive"))
      (node (ref "LED58") (pin "A") (pinfunction "A_A") (pintype "passive"))
      (node (ref "LED59") (pin "C") (pinfunction "C_C") (pintype "passive"))
      (node (ref "LED60") (pin "A") (pinfunction "A_A") (pintype "passive"))
    )
    (net (code "11") (name "Net-(LED62-PadA)") (class "Default")
      (node (ref "LED62") (pin "A") (pinfunction "A_A") (pintype "passive"))
      (node (ref "LED63") (pin "C") (pinfunction "C_C") (pintype "passive"))
      (node (ref "LED64") (pin "A") (pinfunction "A_A") (pintype "passive"))
      (node (ref "LED65") (pin "C") (pinfunction "C_C") (pintype "passive"))
      (node (ref "LED66") (pin "A") (pinfunction "A_A") (pintype "passive"))
      (node (ref "LED67") (pin "C") (pinfunction "C_C") (pintype "passive"))
      (node (ref "LED68") (pin "A") (pinfunction "A_A") (pintype "passive"))
      (node (ref "LED69") (pin "C") (pinfunction "C_C") (pintype "passive"))
      (node (ref "LED70") (pin "A") (pinfunction "A_A") (pintype "passive"))
      (node (ref "LED71") (pin "C") (pinfunction "C_C") (pintype "passive"))
    )
    (net (code "12") (name "Net-(LED72-PadA)") (class "Default")
      (node (ref "LED72") (pin "A") (pinfunction "A_A") (pintype "passive"))
      (node (ref "LED73") (pin "C") (pinfunction "C_C") (pintype "passive"))
      (node (ref "LED74") (pin "A") (pinfunction "A_A") (pintype "passive"))
      (node (ref "LED75") (pin "C") (pinfunction "C_C") (pintype "passive"))
      (node (ref "LED76") (pin "A") (pinfunction "A_A") (pintype "passive"))
      (node (ref "LED77") (pin "C") (pinfunction "C_C") (pintype "passive"))
      (node (ref "LED78") (pin "A") (pinfunction "A_A") (pintype "passive"))
      (node (ref "LED79") (pin "C") (pinfunction "C_C") (pintype "passive"))
      (node (ref "LED80") (pin "A") (pinfunction "A_A") (pintype "passive"))
      (node (ref "LED81") (pin "C") (pinfunction "C_C") (pintype "passive"))
    )
    (net (code "13") (name "Net-(LED82-PadA)") (class "Default")
      (node (ref "LED82") (pin "A") (pinfunction "A_A") (pintype "passive"))
      (node (ref "LED83") (pin "C") (pinfunction "C_C") (pintype "passive"))
      (node (ref "LED84") (pin "A") (pinfunction "A_A") (pintype "passive"))
      (node (ref "LED85") (pin "C") (pinfunction "C_C") (pintype "passive"))
      (node (ref "LED86") (pin "A") (pinfunction "A_A") (pintype "passive"))
      (node (ref "LED87") (pin "C") (pinfunction "C_C") (pintype "passive"))
      (node (ref "LED88") (pin "A") (pinfunction "A_A") (pintype "passive"))
      (node (ref "LED89") (pin "C") (pinfunction "C_C") (pintype "passive"))
      (node (ref "LED90") (pin "A") (pinfunction "A_A") (pintype "passive"))
      (node (ref "LED91") (pin "C") (pinfunction "C_C") (pintype "passive"))
    )
    (net (code "14") (name "Net-(LED100-PadA)") (class "Default")
      (node (ref "LED100") (pin "A") (pinfunction "A_A") (pintype "passive"))
      (node (ref "LED101") (pin "C") (pinfunction "C_C") (pintype "passive"))
      (node (ref "LED92") (pin "A") (pinfunction "A_A") (pintype "passive"))
      (node (ref "LED93") (pin "C") (pinfunction "C_C") (pintype "passive"))
      (node (ref "LED94") (pin "A") (pinfunction "A_A") (pintype "passive"))
      (node (ref "LED95") (pin "C") (pinfunction "C_C") (pintype "passive"))
      (node (ref "LED96") (pin "A") (pinfunction "A_A") (pintype "passive"))
      (node (ref "LED97") (pin "C") (pinfunction "C_C") (pintype "passive"))
      (node (ref "LED98") (pin "A") (pinfunction "A_A") (pintype "passive"))
      (node (ref "LED99") (pin "C") (pinfunction "C_C") (pintype "passive"))
    )
    (net (code "15") (name "Net-(LED100-PadC)") (class "Default")
      (node (ref "LED100") (pin "C") (pinfunction "C_C") (pintype "passive"))
      (node (ref "LED101") (pin "A") (pinfunction "A_A") (pintype "passive"))
      (node (ref "LED159") (pin "A") (pinfunction "A_A") (pintype "passive"))
      (node (ref "LED160") (pin "C") (pinfunction "C_C") (pintype "passive"))
      (node (ref "LED39") (pin "A") (pinfunction "A_A") (pintype "passive"))
      (node (ref "LED40") (pin "C") (pinfunction "C_C") (pintype "passive"))
    )
    (net (code "16") (name "Net-(LED102-PadA)") (class "Default")
      (node (ref "LED102") (pin "A") (pinfunction "A_A") (pintype "passive"))
      (node (ref "LED103") (pin "C") (pinfunction "C_C") (pintype "passive"))
      (node (ref "LED104") (pin "A") (pinfunction "A_A") (pintype "passive"))
      (node (ref "LED105") (pin "C") (pinfunction "C_C") (pintype "passive"))
      (node (ref "LED106") (pin "A") (pinfunction "A_A") (pintype "passive"))
      (node (ref "LED107") (pin "C") (pinfunction "C_C") (pintype "passive"))
      (node (ref "LED108") (pin "A") (pinfunction "A_A") (pintype "passive"))
      (node (ref "LED109") (pin "C") (pinfunction "C_C") (pintype "passive"))
      (node (ref "LED110") (pin "A") (pinfunction "A_A") (pintype "passive"))
      (node (ref "LED111") (pin "C") (pinfunction "C_C") (pintype "passive"))
    )
    (net (code "17") (name "Net-(LED102-PadC)") (class "Default")
      (node (ref "LED102") (pin "C") (pinfunction "C_C") (pintype "passive"))
      (node (ref "LED103") (pin "A") (pinfunction "A_A") (pintype "passive"))
      (node (ref "LED161") (pin "A") (pinfunction "A_A") (pintype "passive"))
      (node (ref "LED162") (pin "C") (pinfunction "C_C") (pintype "passive"))
      (node (ref "LED41") (pin "A") (pinfunction "A_A") (pintype "passive"))
      (node (ref "LED42") (pin "C") (pinfunction "C_C") (pintype "passive"))
    )
    (net (code "18") (name "Net-(LED104-PadC)") (class "Default")
      (node (ref "LED104") (pin "C") (pinfunction "C_C") (pintype "passive"))
      (node (ref "LED105") (pin "A") (pinfunction "A_A") (pintype "passive"))
      (node (ref "LED163") (pin "A") (pinfunction "A_A") (pintype "passive"))
      (node (ref "LED164") (pin "C") (pinfunction "C_C") (pintype "passive"))
      (node (ref "LED43") (pin "A") (pinfunction "A_A") (pintype "passive"))
      (node (ref "LED44") (pin "C") (pinfunction "C_C") (pintype "passive"))
    )
    (net (code "19") (name "Net-(LED106-PadC)") (class "Default")
      (node (ref "LED106") (pin "C") (pinfunction "C_C") (pintype "passive"))
      (node (ref "LED107") (pin "A") (pinfunction "A_A") (pintype "passive"))
      (node (ref "LED165") (pin "A") (pinfunction "A_A") (pintype "passive"))
      (node (ref "LED166") (pin "C") (pinfunction "C_C") (pintype "passive"))
      (node (ref "LED45") (pin "A") (pinfunction "A_A") (pintype "passive"))
      (node (ref "LED46") (pin "C") (pinfunction "C_C") (pintype "passive"))
    )
    (net (code "20") (name "Net-(LED108-PadC)") (class "Default")
      (node (ref "LED108") (pin "C") (pinfunction "C_C") (pintype "passive"))
      (node (ref "LED109") (pin "A") (pinfunction "A_A") (pintype "passive"))
      (node (ref "LED167") (pin "A") (pinfunction "A_A") (pintype "passive"))
      (node (ref "LED168") (pin "C") (pinfunction "C_C") (pintype "passive"))
      (node (ref "LED47") (pin "A") (pinfunction "A_A") (pintype "passive"))
      (node (ref "LED48") (pin "C") (pinfunction "C_C") (pintype "passive"))
    )
    (net (code "21") (name "Net-(LED110-PadC)") (class "Default")
      (node (ref "LED110") (pin "C") (pinfunction "C_C") (pintype "passive"))
      (node (ref "LED111") (pin "A") (pinfunction "A_A") (pintype "passive"))
      (node (ref "LED169") (pin "A") (pinfunction "A_A") (pintype "passive"))
      (node (ref "LED170") (pin "C") (pinfunction "C_C") (pintype "passive"))
      (node (ref "LED49") (pin "A") (pinfunction "A_A") (pintype "passive"))
      (node (ref "LED50") (pin "C") (pinfunction "C_C") (pintype "passive"))
    )
    (net (code "22") (name "Net-(LED112-PadA)") (class "Default")
      (node (ref "LED112") (pin "A") (pinfunction "A_A") (pintype "passive"))
      (node (ref "LED113") (pin "C") (pinfunction "C_C") (pintype "passive"))
      (node (ref "LED114") (pin "A") (pinfunction "A_A") (pintype "passive"))
      (node (ref "LED115") (pin "C") (pinfunction "C_C") (pintype "passive"))
      (node (ref "LED116") (pin "A") (pinfunction "A_A") (pintype "passive"))
      (node (ref "LED117") (pin "C") (pinfunction "C_C") (pintype "passive"))
      (node (ref "LED118") (pin "A") (pinfunction "A_A") (pintype "passive"))
      (node (ref "LED119") (pin "C") (pinfunction "C_C") (pintype "passive"))
      (node (ref "LED120") (pin "A") (pinfunction "A_A") (pintype "passive"))
      (node (ref "LED61") (pin "C") (pinfunction "C_C") (pintype "passive"))
    )
    (net (code "23") (name "Net-(LED112-PadC)") (class "Default")
      (node (ref "LED112") (pin "C") (pinfunction "C_C") (pintype "passive"))
      (node (ref "LED113") (pin "A") (pinfunction "A_A") (pintype "passive"))
      (node (ref "LED171") (pin "A") (pinfunction "A_A") (pintype "passive"))
      (node (ref "LED172") (pin "C") (pinfunction "C_C") (pintype "passive"))
      (node (ref "LED51") (pin "A") (pinfunction "A_A") (pintype "passive"))
      (node (ref "LED52") (pin "C") (pinfunction "C_C") (pintype "passive"))
    )
    (net (code "24") (name "Net-(LED114-PadC)") (class "Default")
      (node (ref "LED114") (pin "C") (pinfunction "C_C") (pintype "passive"))
      (node (ref "LED115") (pin "A") (pinfunction "A_A") (pintype "passive"))
      (node (ref "LED173") (pin "A") (pinfunction "A_A") (pintype "passive"))
      (node (ref "LED174") (pin "C") (pinfunction "C_C") (pintype "passive"))
      (node (ref "LED53") (pin "A") (pinfunction "A_A") (pintype "passive"))
      (node (ref "LED54") (pin "C") (pinfunction "C_C") (pintype "passive"))
    )
    (net (code "25") (name "Net-(LED116-PadC)") (class "Default")
      (node (ref "LED116") (pin "C") (pinfunction "C_C") (pintype "passive"))
      (node (ref "LED117") (pin "A") (pinfunction "A_A") (pintype "passive"))
      (node (ref "LED175") (pin "A") (pinfunction "A_A") (pintype "passive"))
      (node (ref "LED176") (pin "C") (pinfunction "C_C") (pintype "passive"))
      (node (ref "LED55") (pin "A") (pinfunction "A_A") (pintype "passive"))
      (node (ref "LED56") (pin "C") (pinfunction "C_C") (pintype "passive"))
    )
    (net (code "26") (name "Net-(LED118-PadC)") (class "Default")
      (node (ref "LED118") (pin "C") (pinfunction "C_C") (pintype "passive"))
      (node (ref "LED119") (pin "A") (pinfunction "A_A") (pintype "passive"))
      (node (ref "LED177") (pin "A") (pinfunction "A_A") (pintype "passive"))
      (node (ref "LED178") (pin "C") (pinfunction "C_C") (pintype "passive"))
      (node (ref "LED57") (pin "A") (pinfunction "A_A") (pintype "passive"))
      (node (ref "LED58") (pin "C") (pinfunction "C_C") (pintype "passive"))
    )
    (net (code "27") (name "Net-(LED120-PadC)") (class "Default")
      (node (ref "LED120") (pin "C") (pinfunction "C_C") (pintype "passive"))
      (node (ref "LED179") (pin "A") (pinfunction "A_A") (pintype "passive"))
      (node (ref "LED180") (pin "C") (pinfunction "C_C") (pintype "passive"))
      (node (ref "LED59") (pin "A") (pinfunction "A_A") (pintype "passive"))
      (node (ref "LED60") (pin "C") (pinfunction "C_C") (pintype "passive"))
      (node (ref "LED61") (pin "A") (pinfunction "A_A") (pintype "passive"))
    )
    (net (code "28") (name "Net-(LED121-PadC)") (class "Default")
      (node (ref "LED121") (pin "C") (pinfunction "C_C") (pintype "passive"))
      (node (ref "LED122") (pin "A") (pinfunction "A_A") (pintype "passive"))
      (node (ref "LED123") (pin "C") (pinfunction "C_C") (pintype "passive"))
      (node (ref "LED124") (pin "A") (pinfunction "A_A") (pintype "passive"))
      (node (ref "LED125") (pin "C") (pinfunction "C_C") (pintype "passive"))
      (node (ref "LED126") (pin "A") (pinfunction "A_A") (pintype "passive"))
      (node (ref "LED127") (pin "C") (pinfunction "C_C") (pintype "passive"))
      (node (ref "LED128") (pin "A") (pinfunction "A_A") (pintype "passive"))
      (node (ref "LED129") (pin "C") (pinfunction "C_C") (pintype "passive"))
      (node (ref "LED130") (pin "A") (pinfunction "A_A") (pintype "passive"))
    )
    (net (code "29") (name "Net-(LED123-PadA)") (class "Default")
      (node (ref "LED123") (pin "A") (pinfunction "A_A") (pintype "passive"))
      (node (ref "LED124") (pin "C") (pinfunction "C_C") (pintype "passive"))
      (node (ref "LED3") (pin "A") (pinfunction "A_A") (pintype "passive"))
      (node (ref "LED4") (pin "C") (pinfunction "C_C") (pintype "passive"))
      (node (ref "LED64") (pin "C") (pinfunction "C_C") (pintype "passive"))
      (node (ref "LED65") (pin "A") (pinfunction "A_A") (pintype "passive"))
    )
    (net (code "30") (name "Net-(LED125-PadA)") (class "Default")
      (node (ref "LED125") (pin "A") (pinfunction "A_A") (pintype "passive"))
      (node (ref "LED126") (pin "C") (pinfunction "C_C") (pintype "passive"))
      (node (ref "LED5") (pin "A") (pinfunction "A_A") (pintype "passive"))
      (node (ref "LED6") (pin "C") (pinfunction "C_C") (pintype "passive"))
      (node (ref "LED66") (pin "C") (pinfunction "C_C") (pintype "passive"))
      (node (ref "LED67") (pin "A") (pinfunction "A_A") (pintype "passive"))
    )
    (net (code "31") (name "Net-(LED127-PadA)") (class "Default")
      (node (ref "LED127") (pin "A") (pinfunction "A_A") (pintype "passive"))
      (node (ref "LED128") (pin "C") (pinfunction "C_C") (pintype "passive"))
      (node (ref "LED68") (pin "C") (pinfunction "C_C") (pintype "passive"))
      (node (ref "LED69") (pin "A") (pinfunction "A_A") (pintype "passive"))
      (node (ref "LED7") (pin "A") (pinfunction "A_A") (pintype "passive"))
      (node (ref "LED8") (pin "C") (pinfunction "C_C") (pintype "passive"))
    )
    (net (code "32") (name "Net-(LED131-PadC)") (class "Default")
      (node (ref "LED131") (pin "C") (pinfunction "C_C") (pintype "passive"))
      (node (ref "LED132") (pin "A") (pinfunction "A_A") (pintype "passive"))
      (node (ref "LED133") (pin "C") (pinfunction "C_C") (pintype "passive"))
      (node (ref "LED134") (pin "A") (pinfunction "A_A") (pintype "passive"))
      (node (ref "LED135") (pin "C") (pinfunction "C_C") (pintype "passive"))
      (node (ref "LED136") (pin "A") (pinfunction "A_A") (pintype "passive"))
      (node (ref "LED137") (pin "C") (pinfunction "C_C") (pintype "passive"))
      (node (ref "LED138") (pin "A") (pinfunction "A_A") (pintype "passive"))
      (node (ref "LED139") (pin "C") (pinfunction "C_C") (pintype "passive"))
      (node (ref "LED140") (pin "A") (pinfunction "A_A") (pintype "passive"))
    )
    (net (code "33") (name "Net-(LED135-PadA)") (class "Default")
      (node (ref "LED135") (pin "A") (pinfunction "A_A") (pintype "passive"))
      (node (ref "LED136") (pin "C") (pinfunction "C_C") (pintype "passive"))
      (node (ref "LED15") (pin "A") (pinfunction "A_A") (pintype "passive"))
      (node (ref "LED16") (pin "C") (pinfunction "C_C") (pintype "passive"))
      (node (ref "LED76") (pin "C") (pinfunction "C_C") (pintype "passive"))
      (node (ref "LED77") (pin "A") (pinfunction "A_A") (pintype "passive"))
    )
    (net (code "34") (name "Net-(LED137-PadA)") (class "Default")
      (node (ref "LED137") (pin "A") (pinfunction "A_A") (pintype "passive"))
      (node (ref "LED138") (pin "C") (pinfunction "C_C") (pintype "passive"))
      (node (ref "LED17") (pin "A") (pinfunction "A_A") (pintype "passive"))
      (node (ref "LED18") (pin "C") (pinfunction "C_C") (pintype "passive"))
      (node (ref "LED78") (pin "C") (pinfunction "C_C") (pintype "passive"))
      (node (ref "LED79") (pin "A") (pinfunction "A_A") (pintype "passive"))
    )
    (net (code "35") (name "Net-(LED139-PadA)") (class "Default")
      (node (ref "LED139") (pin "A") (pinfunction "A_A") (pintype "passive"))
      (node (ref "LED140") (pin "C") (pinfunction "C_C") (pintype "passive"))
      (node (ref "LED19") (pin "A") (pinfunction "A_A") (pintype "passive"))
      (node (ref "LED20") (pin "C") (pinfunction "C_C") (pintype "passive"))
      (node (ref "LED80") (pin "C") (pinfunction "C_C") (pintype "passive"))
      (node (ref "LED81") (pin "A") (pinfunction "A_A") (pintype "passive"))
    )
    (net (code "36") (name "Net-(LED141-PadA)") (class "Default")
      (node (ref "LED141") (pin "A") (pinfunction "A_A") (pintype "passive"))
      (node (ref "LED142") (pin "C") (pinfunction "C_C") (pintype "passive"))
      (node (ref "LED21") (pin "A") (pinfunction "A_A") (pintype "passive"))
      (node (ref "LED22") (pin "C") (pinfunction "C_C") (pintype "passive"))
      (node (ref "LED82") (pin "C") (pinfunction "C_C") (pintype "passive"))
      (node (ref "LED83") (pin "A") (pinfunction "A_A") (pintype "passive"))
    )
    (net (code "37") (name "Net-(LED141-PadC)") (class "Default")
      (node (ref "LED141") (pin "C") (pinfunction "C_C") (pintype "passive"))
      (node (ref "LED142") (pin "A") (pinfunction "A_A") (pintype "passive"))
      (node (ref "LED143") (pin "C") (pinfunction "C_C") (pintype "passive"))
      (node (ref "LED144") (pin "A") (pinfunction "A_A") (pintype "passive"))
      (node (ref "LED145") (pin "C") (pinfunction "C_C") (pintype "passive"))
      (node (ref "LED146") (pin "A") (pinfunction "A_A") (pintype "passive"))
      (node (ref "LED147") (pin "C") (pinfunction "C_C") (pintype "passive"))
      (node (ref "LED148") (pin "A") (pinfunction "A_A") (pintype "passive"))
      (node (ref "LED149") (pin "C") (pinfunction "C_C") (pintype "passive"))
      (node (ref "LED150") (pin "A") (pinfunction "A_A") (pintype "passive"))
    )
    (net (code "38") (name "Net-(LED143-PadA)") (class "Default")
      (node (ref "LED143") (pin "A") (pinfunction "A_A") (pintype "passive"))
      (node (ref "LED144") (pin "C") (pinfunction "C_C") (pintype "passive"))
      (node (ref "LED23") (pin "A") (pinfunction "A_A") (pintype "passive"))
      (node (ref "LED24") (pin "C") (pinfunction "C_C") (pintype "passive"))
      (node (ref "LED84") (pin "C") (pinfunction "C_C") (pintype "passive"))
      (node (ref "LED85") (pin "A") (pinfunction "A_A") (pintype "passive"))
    )
    (net (code "39") (name "Net-(LED145-PadA)") (class "Default")
      (node (ref "LED145") (pin "A") (pinfunction "A_A") (pintype "passive"))
      (node (ref "LED146") (pin "C") (pinfunction "C_C") (pintype "passive"))
      (node (ref "LED25") (pin "A") (pinfunction "A_A") (pintype "passive"))
      (node (ref "LED26") (pin "C") (pinfunction "C_C") (pintype "passive"))
      (node (ref "LED86") (pin "C") (pinfunction "C_C") (pintype "passive"))
      (node (ref "LED87") (pin "A") (pinfunction "A_A") (pintype "passive"))
    )
    (net (code "40") (name "Net-(LED147-PadA)") (class "Default")
      (node (ref "LED147") (pin "A") (pinfunction "A_A") (pintype "passive"))
      (node (ref "LED148") (pin "C") (pinfunction "C_C") (pintype "passive"))
      (node (ref "LED27") (pin "A") (pinfunction "A_A") (pintype "passive"))
      (node (ref "LED28") (pin "C") (pinfunction "C_C") (pintype "passive"))
      (node (ref "LED88") (pin "C") (pinfunction "C_C") (pintype "passive"))
      (node (ref "LED89") (pin "A") (pinfunction "A_A") (pintype "passive"))
    )
    (net (code "41") (name "Net-(LED149-PadA)") (class "Default")
      (node (ref "LED149") (pin "A") (pinfunction "A_A") (pintype "passive"))
      (node (ref "LED150") (pin "C") (pinfunction "C_C") (pintype "passive"))
      (node (ref "LED29") (pin "A") (pinfunction "A_A") (pintype "passive"))
      (node (ref "LED30") (pin "C") (pinfunction "C_C") (pintype "passive"))
      (node (ref "LED90") (pin "C") (pinfunction "C_C") (pintype "passive"))
      (node (ref "LED91") (pin "A") (pinfunction "A_A") (pintype "passive"))
    )
    (net (code "42") (name "Net-(LED151-PadA)") (class "Default")
      (node (ref "LED151") (pin "A") (pinfunction "A_A") (pintype "passive"))
      (node (ref "LED152") (pin "C") (pinfunction "C_C") (pintype "passive"))
      (node (ref "LED31") (pin "A") (pinfunction "A_A") (pintype "passive"))
      (node (ref "LED32") (pin "C") (pinfunction "C_C") (pintype "passive"))
      (node (ref "LED92") (pin "C") (pinfunction "C_C") (pintype "passive"))
      (node (ref "LED93") (pin "A") (pinfunction "A_A") (pintype "passive"))
    )
    (net (code "43") (name "Net-(LED151-PadC)") (class "Default")
      (node (ref "LED151") (pin "C") (pinfunction "C_C") (pintype "passive"))
      (node (ref "LED152") (pin "A") (pinfunction "A_A") (pintype "passive"))
      (node (ref "LED153") (pin "C") (pinfunction "C_C") (pintype "passive"))
      (node (ref "LED154") (pin "A") (pinfunction "A_A") (pintype "passive"))
      (node (ref "LED155") (pin "C") (pinfunction "C_C") (pintype "passive"))
      (node (ref "LED156") (pin "A") (pinfunction "A_A") (pintype "passive"))
      (node (ref "LED157") (pin "C") (pinfunction "C_C") (pintype "passive"))
      (node (ref "LED158") (pin "A") (pinfunction "A_A") (pintype "passive"))
      (node (ref "LED159") (pin "C") (pinfunction "C_C") (pintype "passive"))
      (node (ref "LED160") (pin "A") (pinfunction "A_A") (pintype "passive"))
    )
    (net (code "44") (name "Net-(LED153-PadA)") (class "Default")
      (node (ref "LED153") (pin "A") (pinfunction "A_A") (pintype "passive"))
      (node (ref "LED154") (pin "C") (pinfunction "C_C") (pintype "passive"))
      (node (ref "LED33") (pin "A") (pinfunction "A_A") (pintype "passive"))
      (node (ref "LED34") (pin "C") (pinfunction "C_C") (pintype "passive"))
      (node (ref "LED94") (pin "C") (pinfunction "C_C") (pintype "passive"))
      (node (ref "LED95") (pin "A") (pinfunction "A_A") (pintype "passive"))
    )
    (net (code "45") (name "Net-(LED155-PadA)") (class "Default")
      (node (ref "LED155") (pin "A") (pinfunction "A_A") (pintype "passive"))
      (node (ref "LED156") (pin "C") (pinfunction "C_C") (pintype "passive"))
      (node (ref "LED35") (pin "A") (pinfunction "A_A") (pintype "passive"))
      (node (ref "LED36") (pin "C") (pinfunction "C_C") (pintype "passive"))
      (node (ref "LED96") (pin "C") (pinfunction "C_C") (pintype "passive"))
      (node (ref "LED97") (pin "A") (pinfunction "A_A") (pintype "passive"))
    )
    (net (code "46") (name "Net-(LED157-PadA)") (class "Default")
      (node (ref "LED157") (pin "A") (pinfunction "A_A") (pintype "passive"))
      (node (ref "LED158") (pin "C") (pinfunction "C_C") (pintype "passive"))
      (node (ref "LED37") (pin "A") (pinfunction "A_A") (pintype "passive"))
      (node (ref "LED38") (pin "C") (pinfunction "C_C") (pintype "passive"))
      (node (ref "LED98") (pin "C") (pinfunction "C_C") (pintype "passive"))
      (node (ref "LED99") (pin "A") (pinfunction "A_A") (pintype "passive"))
    )
    (net (code "47") (name "Net-(LED161-PadC)") (class "Default")
      (node (ref "LED161") (pin "C") (pinfunction "C_C") (pintype "passive"))
      (node (ref "LED162") (pin "A") (pinfunction "A_A") (pintype "passive"))
      (node (ref "LED163") (pin "C") (pinfunction "C_C") (pintype "passive"))
      (node (ref "LED164") (pin "A") (pinfunction "A_A") (pintype "passive"))
      (node (ref "LED165") (pin "C") (pinfunction "C_C") (pintype "passive"))
      (node (ref "LED166") (pin "A") (pinfunction "A_A") (pintype "passive"))
      (node (ref "LED167") (pin "C") (pinfunction "C_C") (pintype "passive"))
      (node (ref "LED168") (pin "A") (pinfunction "A_A") (pintype "passive"))
      (node (ref "LED169") (pin "C") (pinfunction "C_C") (pintype "passive"))
      (node (ref "LED170") (pin "A") (pinfunction "A_A") (pintype "passive"))
    )
    (net (code "48") (name "Net-(LED171-PadC)") (class "Default")
      (node (ref "LED171") (pin "C") (pinfunction "C_C") (pintype "passive"))
      (node (ref "LED172") (pin "A") (pinfunction "A_A") (pintype "passive"))
      (node (ref "LED173") (pin "C") (pinfunction "C_C") (pintype "passive"))
      (node (ref "LED174") (pin "A") (pinfunction "A_A") (pintype "passive"))
      (node (ref "LED175") (pin "C") (pinfunction "C_C") (pintype "passive"))
      (node (ref "LED176") (pin "A") (pinfunction "A_A") (pintype "passive"))
      (node (ref "LED177") (pin "C") (pinfunction "C_C") (pintype "passive"))
      (node (ref "LED178") (pin "A") (pinfunction "A_A") (pintype "passive"))
      (node (ref "LED179") (pin "C") (pinfunction "C_C") (pintype "passive"))
      (node (ref "LED180") (pin "A") (pinfunction "A_A") (pintype "passive"))
    )
    (net (code "49") (name "unconnected-(H1-PadP1)") (class "Default")
      (node (ref "H1") (pin "P1") (pinfunction "P1_P1") (pintype "bidirectional"))
    )
    (net (code "50") (name "unconnected-(H1-PadP2)") (class "Default")
      (node (ref "H1") (pin "P2") (pinfunction "P2_P2") (pintype "bidirectional"))
    )
    (net (code "51") (name "unconnected-(H1-PadP3)") (class "Default")
      (node (ref "H1") (pin "P3") (pinfunction "P3_P3") (pintype "bidirectional"))
    )
    (net (code "52") (name "unconnected-(H1-PadP4)") (class "Default")
      (node (ref "H1") (pin "P4") (pinfunction "P4_P4") (pintype "bidirectional"))
    )
    (net (code "53") (name "unconnected-(H1-PadP5)") (class "Default")
      (node (ref "H1") (pin "P5") (pinfunction "P5_P5") (pintype "bidirectional"))
    )
    (net (code "54") (name "unconnected-(H1-PadP6)") (class "Default")
      (node (ref "H1") (pin "P6") (pinfunction "P6_P6") (pintype "bidirectional"))
    )
    (net (code "55") (name "unconnected-(H2-PadP1)") (class "Default")
      (node (ref "H2") (pin "P1") (pinfunction "P1_P1") (pintype "bidirectional"))
    )
    (net (code "56") (name "unconnected-(H2-PadP2)") (class "Default")
      (node (ref "H2") (pin "P2") (pinfunction "P2_P2") (pintype "bidirectional"))
    )
    (net (code "57") (name "unconnected-(H2-PadP3)") (class "Default")
      (node (ref "H2") (pin "P3") (pinfunction "P3_P3") (pintype "bidirectional"))
    )
    (net (code "58") (name "unconnected-(H2-PadP4)") (class "Default")
      (node (ref "H2") (pin "P4") (pinfunction "P4_P4") (pintype "bidirectional"))
    )
    (net (code "59") (name "unconnected-(H2-PadP5)") (class "Default")
      (node (ref "H2") (pin "P5") (pinfunction "P5_P5") (pintype "bidirectional"))
    )
    (net (code "60") (name "unconnected-(H2-PadP6)") (class "Default")
      (node (ref "H2") (pin "P6") (pinfunction "P6_P6") (pintype "bidirectional"))
    )
    (net (code "61") (name "unconnected-(H3-PadP1)") (class "Default")
      (node (ref "H3") (pin "P1") (pinfunction "P1_P1") (pintype "bidirectional"))
    )
    (net (code "62") (name "unconnected-(H3-PadP2)") (class "Default")
      (node (ref "H3") (pin "P2") (pinfunction "P2_P2") (pintype "bidirectional"))
    )
    (net (code "63") (name "unconnected-(H3-PadP3)") (class "Default")
      (node (ref "H3") (pin "P3") (pinfunction "P3_P3") (pintype "bidirectional"))
    )
    (net (code "64") (name "unconnected-(H3-PadP4)") (class "Default")
      (node (ref "H3") (pin "P4") (pinfunction "P4_P4") (pintype "bidirectional"))
    )
    (net (code "65") (name "unconnected-(H3-PadP5)") (class "Default")
      (node (ref "H3") (pin "P5") (pinfunction "P5_P5") (pintype "bidirectional"))
    )
    (net (code "66") (name "unconnected-(H3-PadP6)") (class "Default")
      (node (ref "H3") (pin "P6") (pinfunction "P6_P6") (pintype "bidirectional"))
    )
    (net (code "67") (name "unconnected-(H4-PadP1)") (class "Default")
      (node (ref "H4") (pin "P1") (pinfunction "P1_P1") (pintype "bidirectional"))
    )
    (net (code "68") (name "unconnected-(H4-PadP2)") (class "Default")
      (node (ref "H4") (pin "P2") (pinfunction "P2_P2") (pintype "bidirectional"))
    )
    (net (code "69") (name "unconnected-(H4-PadP3)") (class "Default")
      (node (ref "H4") (pin "P3") (pinfunction "P3_P3") (pintype "bidirectional"))
    )
    (net (code "70") (name "unconnected-(H4-PadP4)") (class "Default")
      (node (ref "H4") (pin "P4") (pinfunction "P4_P4") (pintype "bidirectional"))
    )
    (net (code "71") (name "unconnected-(H4-PadP5)") (class "Default")
      (node (ref "H4") (pin "P5") (pinfunction "P5_P5") (pintype "bidirectional"))
    )
    (net (code "72") (name "unconnected-(H4-PadP6)") (class "Default")
      (node (ref "H4") (pin "P6") (pinfunction "P6_P6") (pintype "bidirectional"))
    )
    (net (code "73") (name "unconnected-(H5-PadP1)") (class "Default")
      (node (ref "H5") (pin "P1") (pinfunction "P1_P1") (pintype "bidirectional"))
    )
    (net (code "74") (name "unconnected-(H5-PadP2)") (class "Default")
      (node (ref "H5") (pin "P2") (pinfunction "P2_P2") (pintype "bidirectional"))
    )
    (net (code "75") (name "unconnected-(H5-PadP3)") (class "Default")
      (node (ref "H5") (pin "P3") (pinfunction "P3_P3") (pintype "bidirectional"))
    )
    (net (code "76") (name "unconnected-(H5-PadP4)") (class "Default")
      (node (ref "H5") (pin "P4") (pinfunction "P4_P4") (pintype "bidirectional"))
    )
    (net (code "77") (name "unconnected-(H5-PadP5)") (class "Default")
      (node (ref "H5") (pin "P5") (pinfunction "P5_P5") (pintype "bidirectional"))
    )
    (net (code "78") (name "unconnected-(H5-PadP6)") (class "Default")
      (node (ref "H5") (pin "P6") (pinfunction "P6_P6") (pintype "bidirectional"))
    )
    (net (code "79") (name "unconnected-(H6-PadP1)") (class "Default")
      (node (ref "H6") (pin "P1") (pinfunction "P1_P1") (pintype "bidirectional"))
    )
    (net (code "80") (name "unconnected-(H6-PadP2)") (class "Default")
      (node (ref "H6") (pin "P2") (pinfunction "P2_P2") (pintype "bidirectional"))
    )
    (net (code "81") (name "unconnected-(H6-PadP3)") (class "Default")
      (node (ref "H6") (pin "P3") (pinfunction "P3_P3") (pintype "bidirectional"))
    )
    (net (code "82") (name "unconnected-(H6-PadP4)") (class "Default")
      (node (ref "H6") (pin "P4") (pinfunction "P4_P4") (pintype "bidirectional"))
    )
    (net (code "83") (name "unconnected-(H6-PadP5)") (class "Default")
      (node (ref "H6") (pin "P5") (pinfunction "P5_P5") (pintype "bidirectional"))
    )
    (net (code "84") (name "unconnected-(H6-PadP6)") (class "Default")
      (node (ref "H6") (pin "P6") (pinfunction "P6_P6") (pintype "bidirectional"))
    )
  )
)
